# Button_LED_Layout_RTK_Express.net
KiCad netlist of a schematic drawn in EAGLE
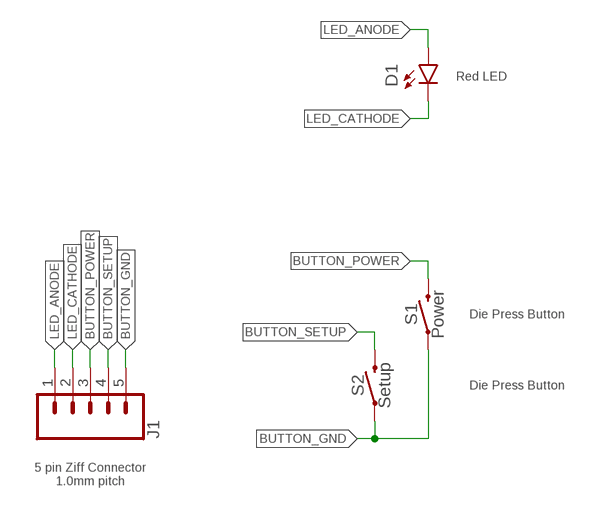
[diagram p0: schematic, sheet 1]

(export (version "E")
  (design (tool "Eeschema 10.0.6"))
  (components
    (comp (ref "D1")
      (value "LED5MM")
      (footprint "eagle-import:LED_5MM")
      (libsource (lib "eagle-import") (part "LED5MM"))
    )
    (comp (ref "J1")
      (value "CONN_05SMD")
      (footprint "eagle-import:1X05_1MM")
      (libsource (lib "eagle-import") (part "CONN_05SMD"))
    )
    (comp (ref "S1")
      (value "Power")
      (footprint "eagle-import:TACTILE_SWITCH_PTH_6.0MM")
      (libsource (lib "eagle-import") (part "MOMENTARY-SWITCH-SPST-PTH-6.0MM"))
    )
    (comp (ref "S2")
      (value "Setup")
      (footprint "eagle-import:TACTILE_SWITCH_PTH_6.0MM")
      (libsource (lib "eagle-import") (part "MOMENTARY-SWITCH-SPST-PTH-6.0MM"))
    )
  )
  (nets
    (net (code "1") (name "BUTTON_GND") (class "Default")
      (node (ref "J1") (pin "5") (pinfunction "5_5") (pintype "passive"))
      (node (ref "S1") (pin "1") (pinfunction "1_1") (pintype "passive"))
      (node (ref "S2") (pin "1") (pinfunction "1_1") (pintype "passive"))
    )
    (net (code "2") (name "BUTTON_POWER") (class "Default")
      (node (ref "J1") (pin "3") (pinfunction "3_3") (pintype "passive"))
      (node (ref "S1") (pin "3") (pinfunction "2_3") (pintype "passive"))
    )
    (net (code "3") (name "BUTTON_SETUP") (class "Default")
      (node (ref "J1") (pin "4") (pinfunction "4_4") (pintype "passive"))
      (node (ref "S2") (pin "3") (pinfunction "2_3") (pintype "passive"))
    )
    (net (code "4") (name "LED_ANODE") (class "Default")
      (node (ref "D1") (pin "A") (pinfunction "A_A") (pintype "passive"))
      (node (ref "J1") (pin "1") (pinfunction "1_1") (pintype "passive"))
    )
    (net (code "5") (name "LED_CATHODE") (class "Default")
      (node (ref "D1") (pin "K") (pinfunction "C_K") (pintype "passive"))
      (node (ref "J1") (pin "2") (pinfunction "2_2") (pintype "passive"))
    )
  )
)
